# BT840_1_27mm_headers.net
KiCad netlist of a schematic drawn in EAGLE
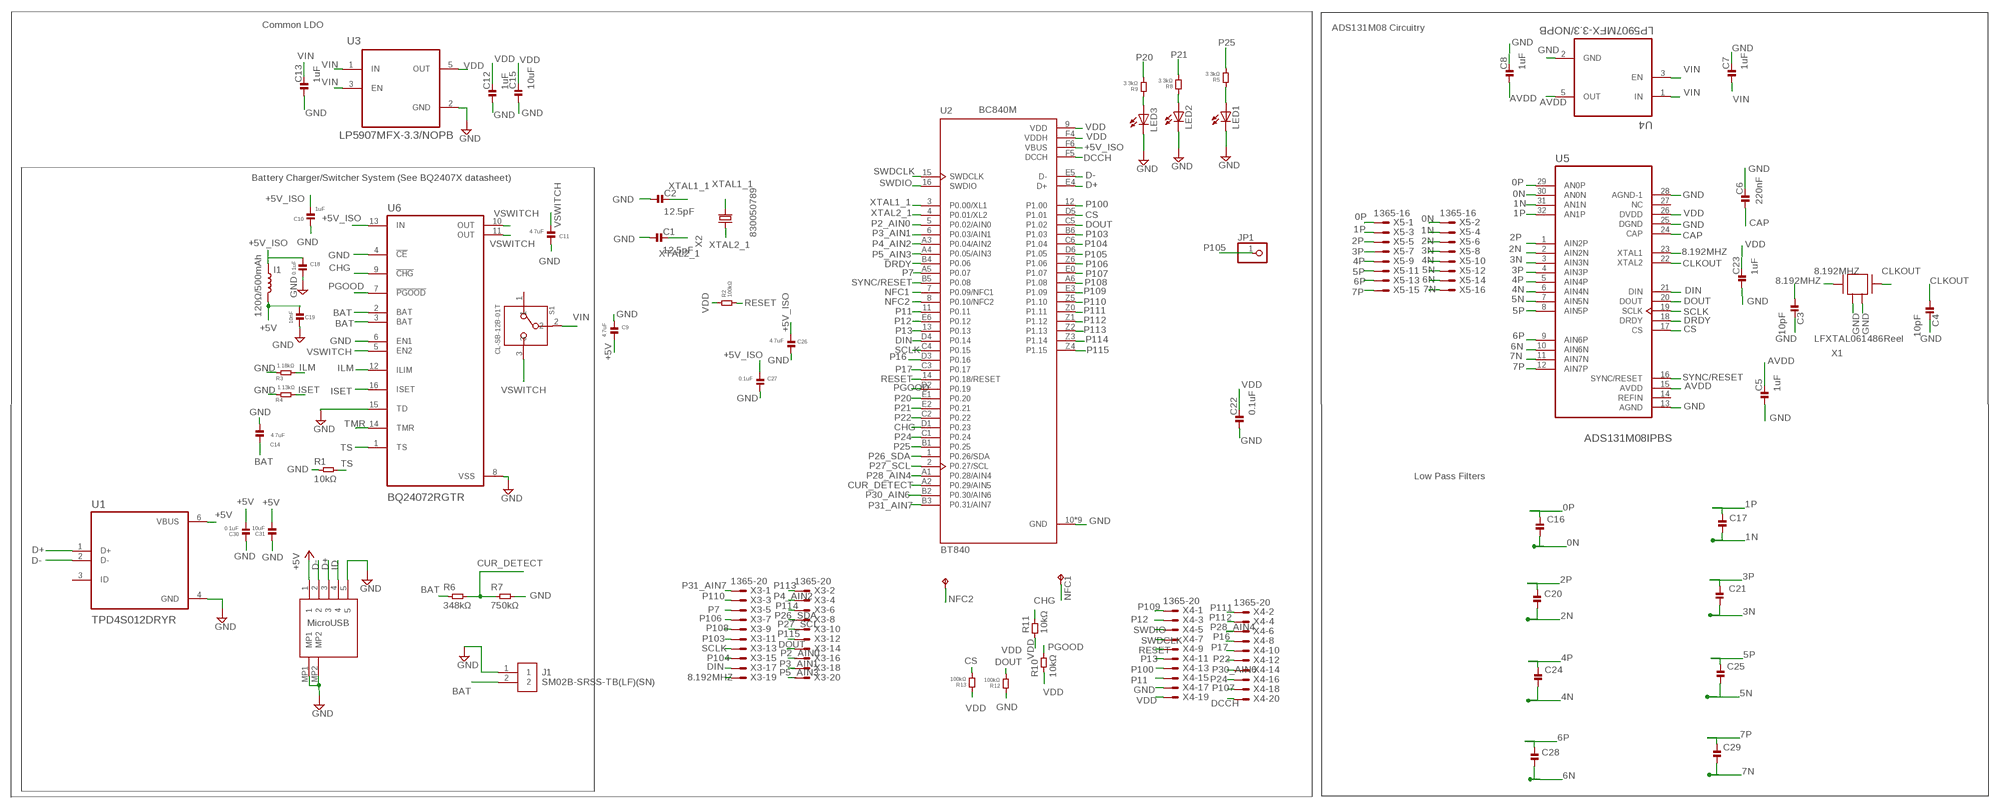
[diagram p0: schematic, sheet 1]

(export (version "E")
  (design (tool "Eeschema 10.0.6"))
  (components
    (comp (ref "C1")
      (value "12.5pF")
      (footprint "eagle-import:0201")
      (libsource (lib "eagle-import") (part "CAPACITOR.0201"))
    )
    (comp (ref "C2")
      (value "12.5pF")
      (footprint "eagle-import:0201")
      (libsource (lib "eagle-import") (part "CAPACITOR.0201"))
    )
    (comp (ref "C3")
      (value "10pF")
      (footprint "eagle-import:0201")
      (libsource (lib "eagle-import") (part "CAPACITOR.0201"))
    )
    (comp (ref "C4")
      (value "10pF")
      (footprint "eagle-import:0201")
      (libsource (lib "eagle-import") (part "CAPACITOR.0201"))
    )
    (comp (ref "C5")
      (value "1uF")
      (footprint "eagle-import:0201")
      (libsource (lib "eagle-import") (part "CAPACITOR.0201"))
    )
    (comp (ref "C6")
      (value "220nF")
      (footprint "eagle-import:0201")
      (libsource (lib "eagle-import") (part "CAPACITOR.0201"))
    )
    (comp (ref "C7")
      (value "1uF")
      (footprint "eagle-import:0201")
      (libsource (lib "eagle-import") (part "CAPACITOR.0201"))
    )
    (comp (ref "C8")
      (value "1uF")
      (footprint "eagle-import:0201")
      (libsource (lib "eagle-import") (part "CAPACITOR.0201"))
    )
    (comp (ref "C9")
      (value "4.7uF")
      (footprint "eagle-import:0201")
      (libsource (lib "eagle-import") (part "CAPACITOR.0201"))
    )
    (comp (ref "C10")
      (value "1uF")
      (footprint "eagle-import:0201")
      (libsource (lib "eagle-import") (part "CAPACITOR.0201"))
    )
    (comp (ref "C11")
      (value "4.7uF")
      (footprint "eagle-import:0201")
      (libsource (lib "eagle-import") (part "CAPACITOR.0201"))
    )
    (comp (ref "C12")
      (value "1uF")
      (footprint "eagle-import:0201")
      (libsource (lib "eagle-import") (part "CAPACITOR.0201"))
    )
    (comp (ref "C13")
      (value "1uF")
      (footprint "eagle-import:0201")
      (libsource (lib "eagle-import") (part "CAPACITOR.0201"))
    )
    (comp (ref "C14")
      (value "4.7uF")
      (footprint "eagle-import:0201")
      (libsource (lib "eagle-import") (part "CAPACITOR.0201"))
    )
    (comp (ref "C15")
      (value "10uF")
      (footprint "eagle-import:0402")
      (libsource (lib "eagle-import") (part "CAPACITOR.0402"))
    )
    (comp (ref "C16")
      (value "100pF")
      (footprint "eagle-import:0201")
      (libsource (lib "eagle-import") (part "CAPACITOR.0201"))
    )
    (comp (ref "C17")
      (value "100pF")
      (footprint "eagle-import:0201")
      (libsource (lib "eagle-import") (part "CAPACITOR.0201"))
    )
    (comp (ref "C18")
      (value "0.1uF")
      (footprint "eagle-import:0201")
      (libsource (lib "eagle-import") (part "CAPACITOR.0201"))
    )
    (comp (ref "C19")
      (value "10nF")
      (footprint "eagle-import:0201")
      (libsource (lib "eagle-import") (part "CAPACITOR.0201"))
    )
    (comp (ref "C20")
      (value "100pF")
      (footprint "eagle-import:0201")
      (libsource (lib "eagle-import") (part "CAPACITOR.0201"))
    )
    (comp (ref "C21")
      (value "100pF")
      (footprint "eagle-import:0201")
      (libsource (lib "eagle-import") (part "CAPACITOR.0201"))
    )
    (comp (ref "C22")
      (value "0.1uF")
      (footprint "eagle-import:0201")
      (libsource (lib "eagle-import") (part "CAPACITOR.0201"))
    )
    (comp (ref "C23")
      (value "1uF")
      (footprint "eagle-import:0201")
      (libsource (lib "eagle-import") (part "CAPACITOR.0201"))
    )
    (comp (ref "C24")
      (value "100pF")
      (footprint "eagle-import:0201")
      (libsource (lib "eagle-import") (part "CAPACITOR.0201"))
    )
    (comp (ref "C25")
      (value "100pF")
      (footprint "eagle-import:0201")
      (libsource (lib "eagle-import") (part "CAPACITOR.0201"))
    )
    (comp (ref "C26")
      (value "4.7uF")
      (footprint "eagle-import:0201")
      (libsource (lib "eagle-import") (part "CAPACITOR.0201"))
    )
    (comp (ref "C27")
      (value "0.1uF")
      (footprint "eagle-import:0201")
      (libsource (lib "eagle-import") (part "CAPACITOR.0201"))
    )
    (comp (ref "C28")
      (value "100pF")
      (footprint "eagle-import:0201")
      (libsource (lib "eagle-import") (part "CAPACITOR.0201"))
    )
    (comp (ref "C29")
      (value "100pF")
      (footprint "eagle-import:0201")
      (libsource (lib "eagle-import") (part "CAPACITOR.0201"))
    )
    (comp (ref "C30")
      (value "0.1uF")
      (footprint "eagle-import:0201")
      (libsource (lib "eagle-import") (part "CAPACITOR.0201"))
    )
    (comp (ref "C31")
      (value "10uF")
      (footprint "eagle-import:0402")
      (libsource (lib "eagle-import") (part "CAPACITOR.0402"))
    )
    (comp (ref "I1")
      (value "120Ω/500mAh")
      (footprint "eagle-import:0402_COILCRAFT")
      (fields (field (name "MOUSER_PART") "994-0402HP-12NXGLU"))
      (libsource (lib "eagle-import") (part "12NH-0402"))
    )
    (comp (ref "J1")
      (value "SM02B-SRSS-TB(LF)(SN)")
      (footprint "eagle-import:SM02B-SRSS-TB(LF)(SN)")
      (fields (field (name "MF") "JST Sales"))
      (libsource (lib "eagle-import") (part "SM02B-SRSS-TB(LF)(SN)"))
    )
    (comp (ref "JP1")
      (value "PINHD-1X1")
      (footprint "eagle-import:1X01")
      (libsource (lib "eagle-import") (part "PINHD-1X1"))
    )
    (comp (ref "LED1")
      (value "LEDCHIPLED_0603")
      (footprint "eagle-import:CHIPLED_0603")
      (libsource (lib "eagle-import") (part "LEDCHIPLED_0603"))
    )
    (comp (ref "LED2")
      (value "LEDCHIPLED_0603")
      (footprint "eagle-import:CHIPLED_0603")
      (libsource (lib "eagle-import") (part "LEDCHIPLED_0603"))
    )
    (comp (ref "LED3")
      (value "LEDCHIPLED_0603")
      (footprint "eagle-import:CHIPLED_0603")
      (libsource (lib "eagle-import") (part "LEDCHIPLED_0603"))
    )
    (comp (ref "NFC1")
      (value "TPTP14SQ")
      (footprint "eagle-import:TP14SQ")
      (libsource (lib "eagle-import") (part "TPTP14SQ"))
    )
    (comp (ref "NFC2")
      (value "TPTP14SQ")
      (footprint "eagle-import:TP14SQ")
      (libsource (lib "eagle-import") (part "TPTP14SQ"))
    )
    (comp (ref "R1")
      (value "10kΩ")
      (footprint "eagle-import:0201")
      (libsource (lib "eagle-import") (part "RESISTOR.0201"))
    )
    (comp (ref "R2")
      (value "100kΩ")
      (footprint "eagle-import:0201")
      (libsource (lib "eagle-import") (part "RESISTOR.0201"))
    )
    (comp (ref "R3")
      (value "1.18kΩ")
      (footprint "eagle-import:0201")
      (fields (field (name "SPICEPREFIX") "R"))
      (libsource (lib "eagle-import") (part "RESISTOR.0201"))
    )
    (comp (ref "R4")
      (value "1.13kΩ")
      (footprint "eagle-import:0201")
      (libsource (lib "eagle-import") (part "RESISTOR.0201"))
    )
    (comp (ref "R5")
      (value "3.3kΩ")
      (footprint "eagle-import:0201")
      (libsource (lib "eagle-import") (part "RESISTOR.0201"))
    )
    (comp (ref "R6")
      (value "348kΩ")
      (footprint "eagle-import:0201")
      (libsource (lib "eagle-import") (part "RESISTOR.0201"))
    )
    (comp (ref "R7")
      (value "750kΩ")
      (footprint "eagle-import:0201")
      (libsource (lib "eagle-import") (part "RESISTOR.0201"))
    )
    (comp (ref "R8")
      (value "3.3kΩ")
      (footprint "eagle-import:0201")
      (libsource (lib "eagle-import") (part "RESISTOR.0201"))
    )
    (comp (ref "R9")
      (value "3.3kΩ")
      (footprint "eagle-import:0201")
      (libsource (lib "eagle-import") (part "RESISTOR.0201"))
    )
    (comp (ref "R10")
      (value "10kΩ")
      (footprint "eagle-import:0402")
      (libsource (lib "eagle-import") (part "RESISTOR.0402"))
    )
    (comp (ref "R11")
      (value "10kΩ")
      (footprint "eagle-import:0402")
      (libsource (lib "eagle-import") (part "RESISTOR.0402"))
    )
    (comp (ref "R12")
      (value "100kΩ")
      (footprint "eagle-import:0402")
      (libsource (lib "eagle-import") (part "RESISTOR.0402"))
    )
    (comp (ref "R13")
      (value "100kΩ")
      (footprint "eagle-import:0402")
      (libsource (lib "eagle-import") (part "RESISTOR.0402"))
    )
    (comp (ref "S1")
      (value "CL-SB-12B-01T")
      (footprint "eagle-import:CL-SB-12B")
      (fields (field (name "MF") "Nidec Copal"))
      (libsource (lib "eagle-import") (part "CL-SB-12B-01T"))
    )
    (comp (ref "U1")
      (value "TPD4S012DRYR")
      (footprint "eagle-import:PSON50P145X100X60-6N")
      (fields (field (name "MF") "Texas Instruments"))
      (libsource (lib "eagle-import") (part "TPD4S012DRYR"))
    )
    (comp (ref "U2")
      (value "BT840")
      (footprint "eagle-import:XCVR_BT840")
      (fields (field (name "MF") "Fanstel Corp."))
      (libsource (lib "eagle-import") (part "BT840"))
    )
    (comp (ref "U3")
      (value "LP5907MFX-3.3/NOPB")
      (footprint "eagle-import:SOT95P280X145-5N")
      (fields (field (name "MF") "Texas Instruments"))
      (libsource (lib "eagle-import") (part "LP5907MFX-3.3/NOPB"))
    )
    (comp (ref "U4")
      (value "LP5907MFX-3.3/NOPB")
      (footprint "eagle-import:SOT95P280X145-5N")
      (fields (field (name "MF") "Texas Instruments"))
      (libsource (lib "eagle-import") (part "LP5907MFX-3.3/NOPB"))
    )
    (comp (ref "U5")
      (value "ADS131M08IPBS")
      (footprint "eagle-import:QFP50P700X700X120-32N")
      (fields (field (name "MF") "Texas Instruments"))
      (libsource (lib "eagle-import") (part "ADS131M08IPBS"))
    )
    (comp (ref "U6")
      (value "BQ24072RGTR")
      (footprint "eagle-import:QFN50P300X300X100-17N")
      (fields (field (name "MF") "Texas Instruments"))
      (libsource (lib "eagle-import") (part "BQ24072RGTR"))
    )
    (comp (ref "U7")
      (value "DX4R005JJ2R1800")
      (footprint "eagle-import:DX4R005JJ2R1800")
      (fields (field (name "MF") "JAE Electronics"))
      (libsource (lib "eagle-import") (part "DX4R005JJ2R1800"))
    )
    (comp (ref "X1")
      (value "ABM3B-8.000MHZ-B2-T")
      (footprint "eagle-import:ABM3B-8.000MHZ-B2-T")
      (fields
        (field (name "DIGIKEY_PART_NUMBER") "535-9720-2-ND")
        (field (name "MANUFACTURER") "Abracon LLC")
        (field (name "CREATED_BY") "PCBLayout.com")
      )
      (libsource (lib "eagle-import") (part "ABM3B-8.000MHZ-B2-T"))
    )
    (comp (ref "X2")
      (value "FC-12M")
      (footprint "eagle-import:FC-12M")
      (libsource (lib "eagle-import") (part "FC-12M"))
    )
    (comp (ref "X3")
      (value "1365-20")
      (footprint "eagle-import:1365-20")
      (libsource (lib "eagle-import") (part "1365-20"))
    )
    (comp (ref "X4")
      (value "1365-20")
      (footprint "eagle-import:1365-20")
      (libsource (lib "eagle-import") (part "1365-20"))
    )
    (comp (ref "X5")
      (value "1365-16")
      (footprint "eagle-import:1365-16")
      (libsource (lib "eagle-import") (part "1365-16"))
    )
  )
  (nets
    (net (code "1") (name "+5V") (class "Default")
      (node (ref "C19") (pin "2") (pinfunction "2_2") (pintype "bidirectional"))
      (node (ref "C30") (pin "2") (pinfunction "2_2") (pintype "bidirectional"))
      (node (ref "C31") (pin "2") (pinfunction "2_2") (pintype "bidirectional"))
      (node (ref "C9") (pin "2") (pinfunction "2_2") (pintype "bidirectional"))
      (node (ref "I1") (pin "P$2") (pinfunction "2_P$2") (pintype "passive"))
      (node (ref "U1") (pin "6") (pinfunction "VBUS_6") (pintype "power_in"))
      (node (ref "U7") (pin "1") (pinfunction "1_1") (pintype "bidirectional"))
    )
    (net (code "2") (name "+5V_ISO") (class "Default")
      (node (ref "C10") (pin "2") (pinfunction "2_2") (pintype "bidirectional"))
      (node (ref "C18") (pin "1") (pinfunction "1_1") (pintype "bidirectional"))
      (node (ref "C26") (pin "2") (pinfunction "2_2") (pintype "bidirectional"))
      (node (ref "C27") (pin "2") (pinfunction "2_2") (pintype "bidirectional"))
      (node (ref "I1") (pin "P$1") (pinfunction "1_P$1") (pintype "passive"))
      (node (ref "U2") (pin "F6") (pinfunction "VBUS_F6") (pintype "power_in"))
      (node (ref "U6") (pin "13") (pinfunction "IN_13") (pintype "input"))
    )
    (net (code "3") (name "0N") (class "Default")
      (node (ref "C16") (pin "2") (pinfunction "2_2") (pintype "bidirectional"))
      (node (ref "U5") (pin "30") (pinfunction "AN0N_30") (pintype "bidirectional"))
      (node (ref "X5") (pin "2") (pinfunction "S_2") (pintype "passive"))
    )
    (net (code "4") (name "0P") (class "Default")
      (node (ref "C16") (pin "1") (pinfunction "1_1") (pintype "bidirectional"))
      (node (ref "U5") (pin "29") (pinfunction "AN0P_29") (pintype "bidirectional"))
      (node (ref "X5") (pin "1") (pinfunction "S_1") (pintype "passive"))
    )
    (net (code "5") (name "1N") (class "Default")
      (node (ref "C17") (pin "2") (pinfunction "2_2") (pintype "bidirectional"))
      (node (ref "U5") (pin "31") (pinfunction "AN1N_31") (pintype "bidirectional"))
      (node (ref "X5") (pin "4") (pinfunction "S_4") (pintype "passive"))
    )
    (net (code "6") (name "1P") (class "Default")
      (node (ref "C17") (pin "1") (pinfunction "1_1") (pintype "bidirectional"))
      (node (ref "U5") (pin "32") (pinfunction "AN1P_32") (pintype "bidirectional"))
      (node (ref "X5") (pin "3") (pinfunction "S_3") (pintype "passive"))
    )
    (net (code "7") (name "2N") (class "Default")
      (node (ref "C20") (pin "2") (pinfunction "2_2") (pintype "bidirectional"))
      (node (ref "U5") (pin "2") (pinfunction "AIN2N_2") (pintype "input"))
      (node (ref "X5") (pin "6") (pinfunction "S_6") (pintype "passive"))
    )
    (net (code "8") (name "2P") (class "Default")
      (node (ref "C20") (pin "1") (pinfunction "1_1") (pintype "bidirectional"))
      (node (ref "U5") (pin "1") (pinfunction "AIN2P_1") (pintype "input"))
      (node (ref "X5") (pin "5") (pinfunction "S_5") (pintype "passive"))
    )
    (net (code "9") (name "3N") (class "Default")
      (node (ref "C21") (pin "2") (pinfunction "2_2") (pintype "bidirectional"))
      (node (ref "U5") (pin "3") (pinfunction "AIN3N_3") (pintype "input"))
      (node (ref "X5") (pin "8") (pinfunction "S_8") (pintype "passive"))
    )
    (net (code "10") (name "3P") (class "Default")
      (node (ref "C21") (pin "1") (pinfunction "1_1") (pintype "bidirectional"))
      (node (ref "U5") (pin "4") (pinfunction "AIN3P_4") (pintype "input"))
      (node (ref "X5") (pin "7") (pinfunction "S_7") (pintype "passive"))
    )
    (net (code "11") (name "4N") (class "Default")
      (node (ref "C24") (pin "2") (pinfunction "2_2") (pintype "bidirectional"))
      (node (ref "U5") (pin "6") (pinfunction "AIN4N_6") (pintype "input"))
      (node (ref "X5") (pin "10") (pinfunction "S_10") (pintype "passive"))
    )
    (net (code "12") (name "4P") (class "Default")
      (node (ref "C24") (pin "1") (pinfunction "1_1") (pintype "bidirectional"))
      (node (ref "U5") (pin "5") (pinfunction "AIN4P_5") (pintype "input"))
      (node (ref "X5") (pin "9") (pinfunction "S_9") (pintype "passive"))
    )
    (net (code "13") (name "5N") (class "Default")
      (node (ref "C25") (pin "2") (pinfunction "2_2") (pintype "bidirectional"))
      (node (ref "U5") (pin "7") (pinfunction "AIN5N_7") (pintype "input"))
      (node (ref "X5") (pin "12") (pinfunction "S_12") (pintype "passive"))
    )
    (net (code "14") (name "5P") (class "Default")
      (node (ref "C25") (pin "1") (pinfunction "1_1") (pintype "bidirectional"))
      (node (ref "U5") (pin "8") (pinfunction "AIN5P_8") (pintype "input"))
      (node (ref "X5") (pin "11") (pinfunction "S_11") (pintype "passive"))
    )
    (net (code "15") (name "6N") (class "Default")
      (node (ref "C28") (pin "2") (pinfunction "2_2") (pintype "bidirectional"))
      (node (ref "U5") (pin "10") (pinfunction "AIN6N_10") (pintype "input"))
      (node (ref "X5") (pin "14") (pinfunction "S_14") (pintype "passive"))
    )
    (net (code "16") (name "6P") (class "Default")
      (node (ref "C28") (pin "1") (pinfunction "1_1") (pintype "bidirectional"))
      (node (ref "U5") (pin "9") (pinfunction "AIN6P_9") (pintype "input"))
      (node (ref "X5") (pin "13") (pinfunction "S_13") (pintype "passive"))
    )
    (net (code "17") (name "7N") (class "Default")
      (node (ref "C29") (pin "2") (pinfunction "2_2") (pintype "bidirectional"))
      (node (ref "U5") (pin "11") (pinfunction "AIN7N_11") (pintype "input"))
      (node (ref "X5") (pin "16") (pinfunction "S_16") (pintype "passive"))
    )
    (net (code "18") (name "7P") (class "Default")
      (node (ref "C29") (pin "1") (pinfunction "1_1") (pintype "bidirectional"))
      (node (ref "U5") (pin "12") (pinfunction "AIN7P_12") (pintype "input"))
      (node (ref "X5") (pin "15") (pinfunction "S_15") (pintype "passive"))
    )
    (net (code "19") (name "8.192MHZ") (class "Default")
      (node (ref "C3") (pin "1") (pinfunction "1_1") (pintype "bidirectional"))
      (node (ref "U5") (pin "23") (pinfunction "XTAL1_23") (pintype "bidirectional"))
      (node (ref "X1") (pin "1") (pinfunction "1_1") (pintype "passive"))
      (node (ref "X3") (pin "19") (pinfunction "S_19") (pintype "passive"))
    )
    (net (code "20") (name "AVDD") (class "Default")
      (node (ref "C5") (pin "2") (pinfunction "2_2") (pintype "bidirectional"))
      (node (ref "C8") (pin "1") (pinfunction "1_1") (pintype "bidirectional"))
      (node (ref "U4") (pin "5") (pinfunction "OUT_5") (pintype "output"))
      (node (ref "U5") (pin "15") (pinfunction "AVDD_15") (pintype "power_in"))
    )
    (net (code "21") (name "BAT") (class "Default")
      (node (ref "C14") (pin "2") (pinfunction "2_2") (pintype "bidirectional"))
      (node (ref "J1") (pin "2") (pinfunction "2_2") (pintype "bidirectional"))
      (node (ref "R6") (pin "1") (pinfunction "1_1") (pintype "bidirectional"))
      (node (ref "U6") (pin "2") (pinfunction "BAT_2") (pintype "bidirectional"))
      (node (ref "U6") (pin "3") (pinfunction "BAT_3") (pintype "bidirectional"))
    )
    (net (code "22") (name "CAP") (class "Default")
      (node (ref "C6") (pin "1") (pinfunction "1_1") (pintype "bidirectional"))
      (node (ref "U5") (pin "24") (pinfunction "CAP_24") (pintype "bidirectional"))
    )
    (net (code "23") (name "CHG") (class "Default")
      (node (ref "R11") (pin "2") (pinfunction "2_2") (pintype "bidirectional"))
      (node (ref "U2") (pin "D1") (pinfunction "P0.23_D1") (pintype "bidirectional"))
      (node (ref "U6") (pin "9") (pinfunction "~{CHG}_9") (pintype "bidirectional"))
    )
    (net (code "24") (name "CLKOUT") (class "Default")
      (node (ref "C4") (pin "1") (pinfunction "1_1") (pintype "bidirectional"))
      (node (ref "U5") (pin "22") (pinfunction "XTAL2_22") (pintype "bidirectional"))
      (node (ref "X1") (pin "3") (pinfunction "3_3") (pintype "passive"))
    )
    (net (code "25") (name "CS") (class "Default")
      (node (ref "R13") (pin "1") (pinfunction "1_1") (pintype "bidirectional"))
      (node (ref "U2") (pin "D5") (pinfunction "P1.01_D5") (pintype "bidirectional"))
      (node (ref "U5") (pin "17") (pinfunction "CS_17") (pintype "bidirectional"))
    )
    (net (code "26") (name "CUR_DETECT") (class "Default")
      (node (ref "R6") (pin "2") (pinfunction "2_2") (pintype "bidirectional"))
      (node (ref "R7") (pin "1") (pinfunction "1_1") (pintype "bidirectional"))
      (node (ref "U2") (pin "A2") (pinfunction "P0.29/AIN5_A2") (pintype "bidirectional"))
    )
    (net (code "27") (name "D+") (class "Default")
      (node (ref "U1") (pin "1") (pinfunction "D+_1") (pintype "bidirectional"))
      (node (ref "U2") (pin "E4") (pinfunction "D+_E4") (pintype "bidirectional"))
      (node (ref "U7") (pin "3") (pinfunction "3_3") (pintype "bidirectional"))
    )
    (net (code "28") (name "D-") (class "Default")
      (node (ref "U1") (pin "2") (pinfunction "D-_2") (pintype "bidirectional"))
      (node (ref "U2") (pin "E5") (pinfunction "D-_E5") (pintype "bidirectional"))
      (node (ref "U7") (pin "2") (pinfunction "2_2") (pintype "bidirectional"))
    )
    (net (code "29") (name "DCCH") (class "Default")
      (node (ref "U2") (pin "F5") (pinfunction "DCCH_F5") (pintype "power_in"))
      (node (ref "X4") (pin "20") (pinfunction "S_20") (pintype "passive"))
    )
    (net (code "30") (name "DIN") (class "Default")
      (node (ref "U2") (pin "D4") (pinfunction "P0.14_D4") (pintype "bidirectional"))
      (node (ref "U5") (pin "21") (pinfunction "DIN_21") (pintype "input"))
      (node (ref "X3") (pin "17") (pinfunction "S_17") (pintype "passive"))
    )
    (net (code "31") (name "DOUT") (class "Default")
      (node (ref "R12") (pin "1") (pinfunction "1_1") (pintype "bidirectional"))
      (node (ref "U2") (pin "C5") (pinfunction "P1.02_C5") (pintype "bidirectional"))
      (node (ref "U5") (pin "20") (pinfunction "DOUT_20") (pintype "output"))
      (node (ref "X3") (pin "14") (pinfunction "S_14") (pintype "passive"))
    )
    (net (code "32") (name "DRDY") (class "Default")
      (node (ref "U2") (pin "B4") (pinfunction "P0.06_B4") (pintype "bidirectional"))
      (node (ref "U5") (pin "18") (pinfunction "DRDY_18") (pintype "output"))
    )
    (net (code "33") (name "GND") (class "Default")
      (node (ref "C1") (pin "1") (pinfunction "1_1") (pintype "bidirectional"))
      (node (ref "C10") (pin "1") (pinfunction "1_1") (pintype "bidirectional"))
      (node (ref "C11") (pin "1") (pinfunction "1_1") (pintype "bidirectional"))
      (node (ref "C12") (pin "1") (pinfunction "1_1") (pintype "bidirectional"))
      (node (ref "C13") (pin "1") (pinfunction "1_1") (pintype "bidirectional"))
      (node (ref "C14") (pin "1") (pinfunction "1_1") (pintype "bidirectional"))
      (node (ref "C15") (pin "1") (pinfunction "1_1") (pintype "bidirectional"))
      (node (ref "C18") (pin "2") (pinfunction "2_2") (pintype "bidirectional"))
      (node (ref "C19") (pin "1") (pinfunction "1_1") (pintype "bidirectional"))
      (node (ref "C2") (pin "1") (pinfunction "1_1") (pintype "bidirectional"))
      (node (ref "C22") (pin "1") (pinfunction "1_1") (pintype "bidirectional"))
      (node (ref "C23") (pin "1") (pinfunction "1_1") (pintype "bidirectional"))
      (node (ref "C26") (pin "1") (pinfunction "1_1") (pintype "bidirectional"))
      (node (ref "C27") (pin "1") (pinfunction "1_1") (pintype "bidirectional"))
      (node (ref "C3") (pin "2") (pinfunction "2_2") (pintype "bidirectional"))
      (node (ref "C30") (pin "1") (pinfunction "1_1") (pintype "bidirectional"))
      (node (ref "C31") (pin "1") (pinfunction "1_1") (pintype "bidirectional"))
      (node (ref "C4") (pin "2") (pinfunction "2_2") (pintype "bidirectional"))
      (node (ref "C5") (pin "1") (pinfunction "1_1") (pintype "bidirectional"))
      (node (ref "C6") (pin "2") (pinfunction "2_2") (pintype "bidirectional"))
      (node (ref "C7") (pin "2") (pinfunction "2_2") (pintype "bidirectional"))
      (node (ref "C8") (pin "2") (pinfunction "2_2") (pintype "bidirectional"))
      (node (ref "C9") (pin "1") (pinfunction "1_1") (pintype "bidirectional"))
      (node (ref "J1") (pin "1") (pinfunction "1_1") (pintype "bidirectional"))
      (node (ref "LED1") (pin "C") (pinfunction "C_C") (pintype "passive"))
      (node (ref "LED2") (pin "C") (pinfunction "C_C") (pintype "passive"))
      (node (ref "LED3") (pin "C") (pinfunction "C_C") (pintype "passive"))
      (node (ref "R1") (pin "1") (pinfunction "1_1") (pintype "bidirectional"))
      (node (ref "R12") (pin "2") (pinfunction "2_2") (pintype "bidirectional"))
      (node (ref "R3") (pin "1") (pinfunction "1_1") (pintype "bidirectional"))
      (node (ref "R4") (pin "1") (pinfunction "1_1") (pintype "bidirectional"))
      (node (ref "R7") (pin "2") (pinfunction "2_2") (pintype "bidirectional"))
      (node (ref "U1") (pin "4") (pinfunction "GND_4") (pintype "power_in"))
      (node (ref "U2") (pin "10") (pinfunction "GND_10") (pintype "power_in"))
      (node (ref "U2") (pin "A0") (pinfunction "GND_A0") (pintype "power_in"))
      (node (ref "U2") (pin "B0") (pinfunction "GND_B0") (pintype "power_in"))
      (node (ref "U2") (pin "C0") (pinfunction "GND_C0") (pintype "power_in"))
      (node (ref "U2") (pin "D0") (pinfunction "GND_D0") (pintype "power_in"))
      (node (ref "U2") (pin "F0") (pinfunction "GND_F0") (pintype "power_in"))
      (node (ref "U2") (pin "F1") (pinfunction "GND_F1") (pintype "power_in"))
      (node (ref "U2") (pin "F2") (pinfunction "GND_F2") (pintype "power_in"))
      (node (ref "U2") (pin "F3") (pinfunction "GND_F3") (pintype "power_in"))
      (node (ref "U3") (pin "2") (pinfunction "GND_2") (pintype "power_in"))
      (node (ref "U4") (pin "2") (pinfunction "GND_2") (pintype "power_in"))
      (node (ref "U5") (pin "13") (pinfunction "AGND_13") (pintype "power_in"))
      (node (ref "U5") (pin "25") (pinfunction "DGND_25") (pintype "power_in"))
      (node (ref "U5") (pin "28") (pinfunction "AGND-1_28") (pintype "power_in"))
      (node (ref "U6") (pin "15") (pinfunction "TD_15") (pintype "bidirectional"))
      (node (ref "U6") (pin "4") (pinfunction "~{CE}_4") (pintype "bidirectional"))
      (node (ref "U6") (pin "6") (pinfunction "EN1_6") (pintype "bidirectional"))
      (node (ref "U6") (pin "8") (pinfunction "VSS_8") (pintype "power_in"))
      (node (ref "U7") (pin "5") (pinfunction "5_5") (pintype "bidirectional"))
      (node (ref "U7") (pin "MP1") (pinfunction "MP1_MP1") (pintype "bidirectional"))
      (node (ref "U7") (pin "MP2") (pinfunction "MP2_MP2") (pintype "bidirectional"))
      (node (ref "X1") (pin "2") (pinfunction "2_2") (pintype "passive"))
      (node (ref "X1") (pin "4") (pinfunction "4_4") (pintype "passive"))
      (node (ref "X4") (pin "17") (pinfunction "S_17") (pintype "passive"))
    )
    (net (code "34") (name "ID") (class "Default")
      (node (ref "U7") (pin "4") (pinfunction "4_4") (pintype "bidirectional"))
    )
    (net (code "35") (name "ILM") (class "Default")
      (node (ref "R3") (pin "2") (pinfunction "2_2") (pintype "bidirectional"))
      (node (ref "U6") (pin "12") (pinfunction "ILIM_12") (pintype "bidirectional"))
    )
    (net (code "36") (name "ISET") (class "Default")
      (node (ref "R4") (pin "2") (pinfunction "2_2") (pintype "bidirectional"))
      (node (ref "U6") (pin "16") (pinfunction "ISET_16") (pintype "bidirectional"))
    )
    (net (code "37") (name "NFC1") (class "Default")
      (node (ref "NFC2") (pin "TP") (pinfunction "TP_TP") (pintype "input"))
      (node (ref "U2") (pin "7") (pinfunction "P0.09/NFC1_7") (pintype "bidirectional"))
    )
    (net (code "38") (name "NFC2") (class "Default")
      (node (ref "NFC1") (pin "TP") (pinfunction "TP_TP") (pintype "input"))
      (node (ref "U2") (pin "8") (pinfunction "P0.10/NFC2_8") (pintype "bidirectional"))
    )
    (net (code "39") (name "Net-(LED1-PadA)") (class "Default")
      (node (ref "LED1") (pin "A") (pinfunction "A_A") (pintype "passive"))
      (node (ref "R5") (pin "2") (pinfunction "2_2") (pintype "bidirectional"))
    )
    (net (code "40") (name "Net-(LED2-PadA)") (class "Default")
      (node (ref "LED2") (pin "A") (pinfunction "A_A") (pintype "passive"))
      (node (ref "R8") (pin "2") (pinfunction "2_2") (pintype "bidirectional"))
    )
    (net (code "41") (name "Net-(LED3-PadA)") (class "Default")
      (node (ref "LED3") (pin "A") (pinfunction "A_A") (pintype "passive"))
      (node (ref "R9") (pin "2") (pinfunction "2_2") (pintype "bidirectional"))
    )
    (net (code "42") (name "P2_AIN0") (class "Default")
      (node (ref "U2") (pin "5") (pinfunction "P0.02/AIN0_5") (pintype "bidirectional"))
      (node (ref "X3") (pin "16") (pinfunction "S_16") (pintype "passive"))
    )
    (net (code "43") (name "P3_AIN1") (class "Default")
      (node (ref "U2") (pin "6") (pinfunction "P0.03/AIN1_6") (pintype "bidirectional"))
      (node (ref "X3") (pin "18") (pinfunction "S_18") (pintype "passive"))
    )
    (net (code "44") (name "P4_AIN2") (class "Default")
      (node (ref "U2") (pin "A3") (pinfunction "P0.04/AIN2_A3") (pintype "bidirectional"))
      (node (ref "X3") (pin "4") (pinfunction "S_4") (pintype "passive"))
    )
    (net (code "45") (name "P5_AIN3") (class "Default")
      (node (ref "U2") (pin "A4") (pinfunction "P0.05/AIN3_A4") (pintype "bidirectional"))
      (node (ref "X3") (pin "20") (pinfunction "S_20") (pintype "passive"))
    )
    (net (code "46") (name "P7") (class "Default")
      (node (ref "U2") (pin "A5") (pinfunction "P0.07_A5") (pintype "bidirectional"))
      (node (ref "X3") (pin "5") (pinfunction "S_5") (pintype "passive"))
    )
    (net (code "47") (name "P11") (class "Default")
      (node (ref "U2") (pin "11") (pinfunction "P0.11_11") (pintype "bidirectional"))
      (node (ref "X4") (pin "15") (pinfunction "S_15") (pintype "passive"))
    )
    (net (code "48") (name "P12") (class "Default")
      (node (ref "U2") (pin "E6") (pinfunction "P0.12_E6") (pintype "bidirectional"))
      (node (ref "X4") (pin "3") (pinfunction "S_3") (pintype "passive"))
    )
    (net (code "49") (name "P13") (class "Default")
      (node (ref "U2") (pin "13") (pinfunction "P0.13_13") (pintype "bidirectional"))
      (node (ref "X4") (pin "11") (pinfunction "S_11") (pintype "passive"))
    )
    (net (code "50") (name "P16") (class "Default")
      (node (ref "U2") (pin "D3") (pinfunction "P0.16_D3") (pintype "bidirectional"))
      (node (ref "X4") (pin "8") (pinfunction "S_8") (pintype "passive"))
    )
    (net (code "51") (name "P17") (class "Default")
      (node (ref "U2") (pin "C3") (pinfunction "P0.17_C3") (pintype "bidirectional"))
      (node (ref "X4") (pin "10") (pinfunction "S_10") (pintype "passive"))
    )
    (net (code "52") (name "P20") (class "Default")
      (node (ref "R9") (pin "1") (pinfunction "1_1") (pintype "bidirectional"))
      (node (ref "U2") (pin "E1") (pinfunction "P0.20_E1") (pintype "bidirectional"))
    )
    (net (code "53") (name "P21") (class "Default")
      (node (ref "R8") (pin "1") (pinfunction "1_1") (pintype "bidirectional"))
      (node (ref "U2") (pin "E2") (pinfunction "P0.21_E2") (pintype "bidirectional"))
    )
    (net (code "54") (name "P22") (class "Default")
      (node (ref "U2") (pin "C2") (pinfunction "P0.22_C2") (pintype "bidirectional"))
      (node (ref "X4") (pin "12") (pinfunction "S_12") (pintype "passive"))
    )
    (net (code "55") (name "P24") (class "Default")
      (node (ref "U2") (pin "C1") (pinfunction "P0.24_C1") (pintype "bidirectional"))
      (node (ref "X4") (pin "16") (pinfunction "S_16") (pintype "passive"))
    )
    (net (code "56") (name "P25") (class "Default")
      (node (ref "R5") (pin "1") (pinfunction "1_1") (pintype "bidirectional"))
      (node (ref "U2") (pin "B1") (pinfunction "P0.25_B1") (pintype "bidirectional"))
    )
    (net (code "57") (name "P26_SDA") (class "Default")
      (node (ref "U2") (pin "1") (pinfunction "P0.26/SDA_1") (pintype "bidirectional"))
      (node (ref "X3") (pin "8") (pinfunction "S_8") (pintype "passive"))
    )
    (net (code "58") (name "P27_SCL") (class "Default")
      (node (ref "U2") (pin "2") (pinfunction "P0.27/SCL_2") (pintype "bidirectional"))
      (node (ref "X3") (pin "10") (pinfunction "S_10") (pintype "passive"))
    )
    (net (code "59") (name "P28_AIN4") (class "Default")
      (node (ref "U2") (pin "A1") (pinfunction "P0.28/AIN4_A1") (pintype "bidirectional"))
      (node (ref "X4") (pin "6") (pinfunction "S_6") (pintype "passive"))
    )
    (net (code "60") (name "P30_AIN6") (class "Default")
      (node (ref "U2") (pin "B2") (pinfunction "P0.30/AIN6_B2") (pintype "bidirectional"))
      (node (ref "X4") (pin "14") (pinfunction "S_14") (pintype "passive"))
    )
    (net (code "61") (name "P31_AIN7") (class "Default")
      (node (ref "U2") (pin "B3") (pinfunction "P0.31/AIN7_B3") (pintype "bidirectional"))
      (node (ref "X3") (pin "1") (pinfunction "S_1") (pintype "passive"))
    )
    (net (code "62") (name "P100") (class "Default")
      (node (ref "U2") (pin "12") (pinfunction "P1.00_12") (pintype "bidirectional"))
      (node (ref "X4") (pin "13") (pinfunction "S_13") (pintype "passive"))
    )
    (net (code "63") (name "P103") (class "Default")
      (node (ref "U2") (pin "B6") (pinfunction "P1.03_B6") (pintype "bidirectional"))
      (node (ref "X3") (pin "11") (pinfunction "S_11") (pintype "passive"))
    )
    (net (code "64") (name "P104") (class "Default")
      (node (ref "U2") (pin "C6") (pinfunction "P1.04_C6") (pintype "bidirectional"))
      (node (ref "X3") (pin "15") (pinfunction "S_15") (pintype "passive"))
    )
    (net (code "65") (name "P105") (class "Default")
      (node (ref "JP1") (pin "1") (pinfunction "1_1") (pintype "passive"))
      (node (ref "U2") (pin "D6") (pinfunction "P1.05_D6") (pintype "bidirectional"))
    )
    (net (code "66") (name "P106") (class "Default")
      (node (ref "U2") (pin "Z6") (pinfunction "P1.06_Z6") (pintype "bidirectional"))
      (node (ref "X3") (pin "7") (pinfunction "S_7") (pintype "passive"))
    )
    (net (code "67") (name "P107") (class "Default")
      (node (ref "U2") (pin "E0") (pinfunction "P1.07_E0") (pintype "bidirectional"))
      (node (ref "X4") (pin "18") (pinfunction "S_18") (pintype "passive"))
    )
    (net (code "68") (name "P108") (class "Default")
      (node (ref "U2") (pin "A6") (pinfunction "P1.08_A6") (pintype "bidirectional"))
      (node (ref "X3") (pin "9") (pinfunction "S_9") (pintype "passive"))
    )
    (net (code "69") (name "P109") (class "Default")
      (node (ref "U2") (pin "E3") (pinfunction "P1.09_E3") (pintype "bidirectional"))
      (node (ref "X4") (pin "1") (pinfunction "S_1") (pintype "passive"))
    )
    (net (code "70") (name "P110") (class "Default")
      (node (ref "U2") (pin "Z5") (pinfunction "P1.10_Z5") (pintype "bidirectional"))
      (node (ref "X3") (pin "3") (pinfunction "S_3") (pintype "passive"))
    )
    (net (code "71") (name "P111") (class "Default")
      (node (ref "U2") (pin "Z0") (pinfunction "P1.11_Z0") (pintype "bidirectional"))
      (node (ref "X4") (pin "2") (pinfunction "S_2") (pintype "passive"))
    )
    (net (code "72") (name "P112") (class "Default")
      (node (ref "U2") (pin "Z1") (pinfunction "P1.12_Z1") (pintype "bidirectional"))
      (node (ref "X4") (pin "4") (pinfunction "S_4") (pintype "passive"))
    )
    (net (code "73") (name "P113") (class "Default")
      (node (ref "U2") (pin "Z2") (pinfunction "P1.13_Z2") (pintype "bidirectional"))
      (node (ref "X3") (pin "2") (pinfunction "S_2") (pintype "passive"))
    )
    (net (code "74") (name "P114") (class "Default")
      (node (ref "U2") (pin "Z3") (pinfunction "P1.14_Z3") (pintype "bidirectional"))
      (node (ref "X3") (pin "6") (pinfunction "S_6") (pintype "passive"))
    )
    (net (code "75") (name "P115") (class "Default")
      (node (ref "U2") (pin "Z4") (pinfunction "P1.15_Z4") (pintype "bidirectional"))
      (node (ref "X3") (pin "12") (pinfunction "S_12") (pintype "passive"))
    )
    (net (code "76") (name "PGOOD") (class "Default")
      (node (ref "R10") (pin "2") (pinfunction "2_2") (pintype "bidirectional"))
      (node (ref "U2") (pin "D2") (pinfunction "P0.19_D2") (pintype "bidirectional"))
      (node (ref "U6") (pin "7") (pinfunction "~{PGOOD}_7") (pintype "bidirectional"))
    )
    (net (code "77") (name "RESET") (class "Default")
      (node (ref "R2") (pin "1") (pinfunction "1_1") (pintype "bidirectional"))
      (node (ref "U2") (pin "14") (pinfunction "P0.18/RESET_14") (pintype "bidirectional"))
      (node (ref "X4") (pin "9") (pinfunction "S_9") (pintype "passive"))
    )
    (net (code "78") (name "SCLK") (class "Default")
      (node (ref "U2") (pin "C4") (pinfunction "P0.15_C4") (pintype "bidirectional"))
      (node (ref "U5") (pin "19") (pinfunction "SCLK_19") (pintype "input"))
      (node (ref "X3") (pin "13") (pinfunction "S_13") (pintype "passive"))
    )
    (net (code "79") (name "SWDCLK") (class "Default")
      (node (ref "U2") (pin "15") (pinfunction "SWDCLK_15") (pintype "input"))
      (node (ref "X4") (pin "7") (pinfunction "S_7") (pintype "passive"))
    )
    (net (code "80") (name "SWDIO") (class "Default")
      (node (ref "U2") (pin "16") (pinfunction "SWDIO_16") (pintype "bidirectional"))
      (node (ref "X4") (pin "5") (pinfunction "S_5") (pintype "passive"))
    )
    (net (code "81") (name "SYNC{slash}RESET") (class "Default")
      (node (ref "U2") (pin "B5") (pinfunction "P0.08_B5") (pintype "bidirectional"))
      (node (ref "U5") (pin "16") (pinfunction "SYNC/RESET_16") (pintype "bidirectional"))
    )
    (net (code "82") (name "TMR") (class "Default")
      (node (ref "U6") (pin "14") (pinfunction "TMR_14") (pintype "bidirectional"))
    )
    (net (code "83") (name "TS") (class "Default")
      (node (ref "R1") (pin "2") (pinfunction "2_2") (pintype "bidirectional"))
      (node (ref "U6") (pin "1") (pinfunction "TS_1") (pintype "bidirectional"))
    )
    (net (code "84") (name "VDD") (class "Default")
      (node (ref "C12") (pin "2") (pinfunction "2_2") (pintype "bidirectional"))
      (node (ref "C15") (pin "2") (pinfunction "2_2") (pintype "bidirectional"))
      (node (ref "C22") (pin "2") (pinfunction "2_2") (pintype "bidirectional"))
      (node (ref "C23") (pin "2") (pinfunction "2_2") (pintype "bidirectional"))
      (node (ref "R10") (pin "1") (pinfunction "1_1") (pintype "bidirectional"))
      (node (ref "R11") (pin "1") (pinfunction "1_1") (pintype "bidirectional"))
      (node (ref "R13") (pin "2") (pinfunction "2_2") (pintype "bidirectional"))
      (node (ref "R2") (pin "2") (pinfunction "2_2") (pintype "bidirectional"))
      (node (ref "U2") (pin "9") (pinfunction "VDD_9") (pintype "power_in"))
      (node (ref "U2") (pin "F4") (pinfunction "VDDH_F4") (pintype "power_in"))
      (node (ref "U3") (pin "5") (pinfunction "OUT_5") (pintype "output"))
      (node (ref "U5") (pin "26") (pinfunction "DVDD_26") (pintype "power_in"))
      (node (ref "X4") (pin "19") (pinfunction "S_19") (pintype "passive"))
    )
    (net (code "85") (name "VIN") (class "Default")
      (node (ref "C13") (pin "2") (pinfunction "2_2") (pintype "bidirectional"))
      (node (ref "C7") (pin "1") (pinfunction "1_1") (pintype "bidirectional"))
      (node (ref "S1") (pin "2") (pinfunction "2_2") (pintype "bidirectional"))
      (node (ref "U3") (pin "1") (pinfunction "IN_1") (pintype "input"))
      (node (ref "U3") (pin "3") (pinfunction "EN_3") (pintype "input"))
      (node (ref "U4") (pin "1") (pinfunction "IN_1") (pintype "input"))
      (node (ref "U4") (pin "3") (pinfunction "EN_3") (pintype "input"))
    )
    (net (code "86") (name "VSWITCH") (class "Default")
      (node (ref "C11") (pin "2") (pinfunction "2_2") (pintype "bidirectional"))
      (node (ref "S1") (pin "3") (pinfunction "3_3") (pintype "bidirectional"))
      (node (ref "U6") (pin "10") (pinfunction "OUT_10") (pintype "output"))
      (node (ref "U6") (pin "11") (pinfunction "OUT_11") (pintype "output"))
      (node (ref "U6") (pin "5") (pinfunction "EN2_5") (pintype "bidirectional"))
    )
    (net (code "87") (name "XTAL1_1") (class "Default")
      (node (ref "C2") (pin "2") (pinfunction "2_2") (pintype "bidirectional"))
      (node (ref "U2") (pin "3") (pinfunction "P0.00/XL1_3") (pintype "bidirectional"))
      (node (ref "X2") (pin "2") (pinfunction "2_2") (pintype "passive"))
    )
    (net (code "88") (name "XTAL2_1") (class "Default")
      (node (ref "C1") (pin "2") (pinfunction "2_2") (pintype "bidirectional"))
      (node (ref "U2") (pin "4") (pinfunction "P0.01/XL2_4") (pintype "bidirectional"))
      (node (ref "X2") (pin "1") (pinfunction "1_1") (pintype "passive"))
    )
    (net (code "89") (name "unconnected-(S1-Pad1)") (class "Default")
      (node (ref "S1") (pin "1") (pinfunction "1_1") (pintype "bidirectional"))
    )
    (net (code "90") (name "unconnected-(U1-ID-Pad3)") (class "Default")
      (node (ref "U1") (pin "3") (pinfunction "ID_3") (pintype "bidirectional"))
    )
    (net (code "91") (name "unconnected-(U5-NC-Pad27)") (class "Default")
      (node (ref "U5") (pin "27") (pinfunction "NC_27") (pintype "bidirectional"))
    )
    (net (code "92") (name "unconnected-(U5-REFIN-Pad14)") (class "Default")
      (node (ref "U5") (pin "14") (pinfunction "REFIN_14") (pintype "input"))
    )
  )
)
